# booster_2_01.net
KiCad netlist of a schematic drawn in EAGLE
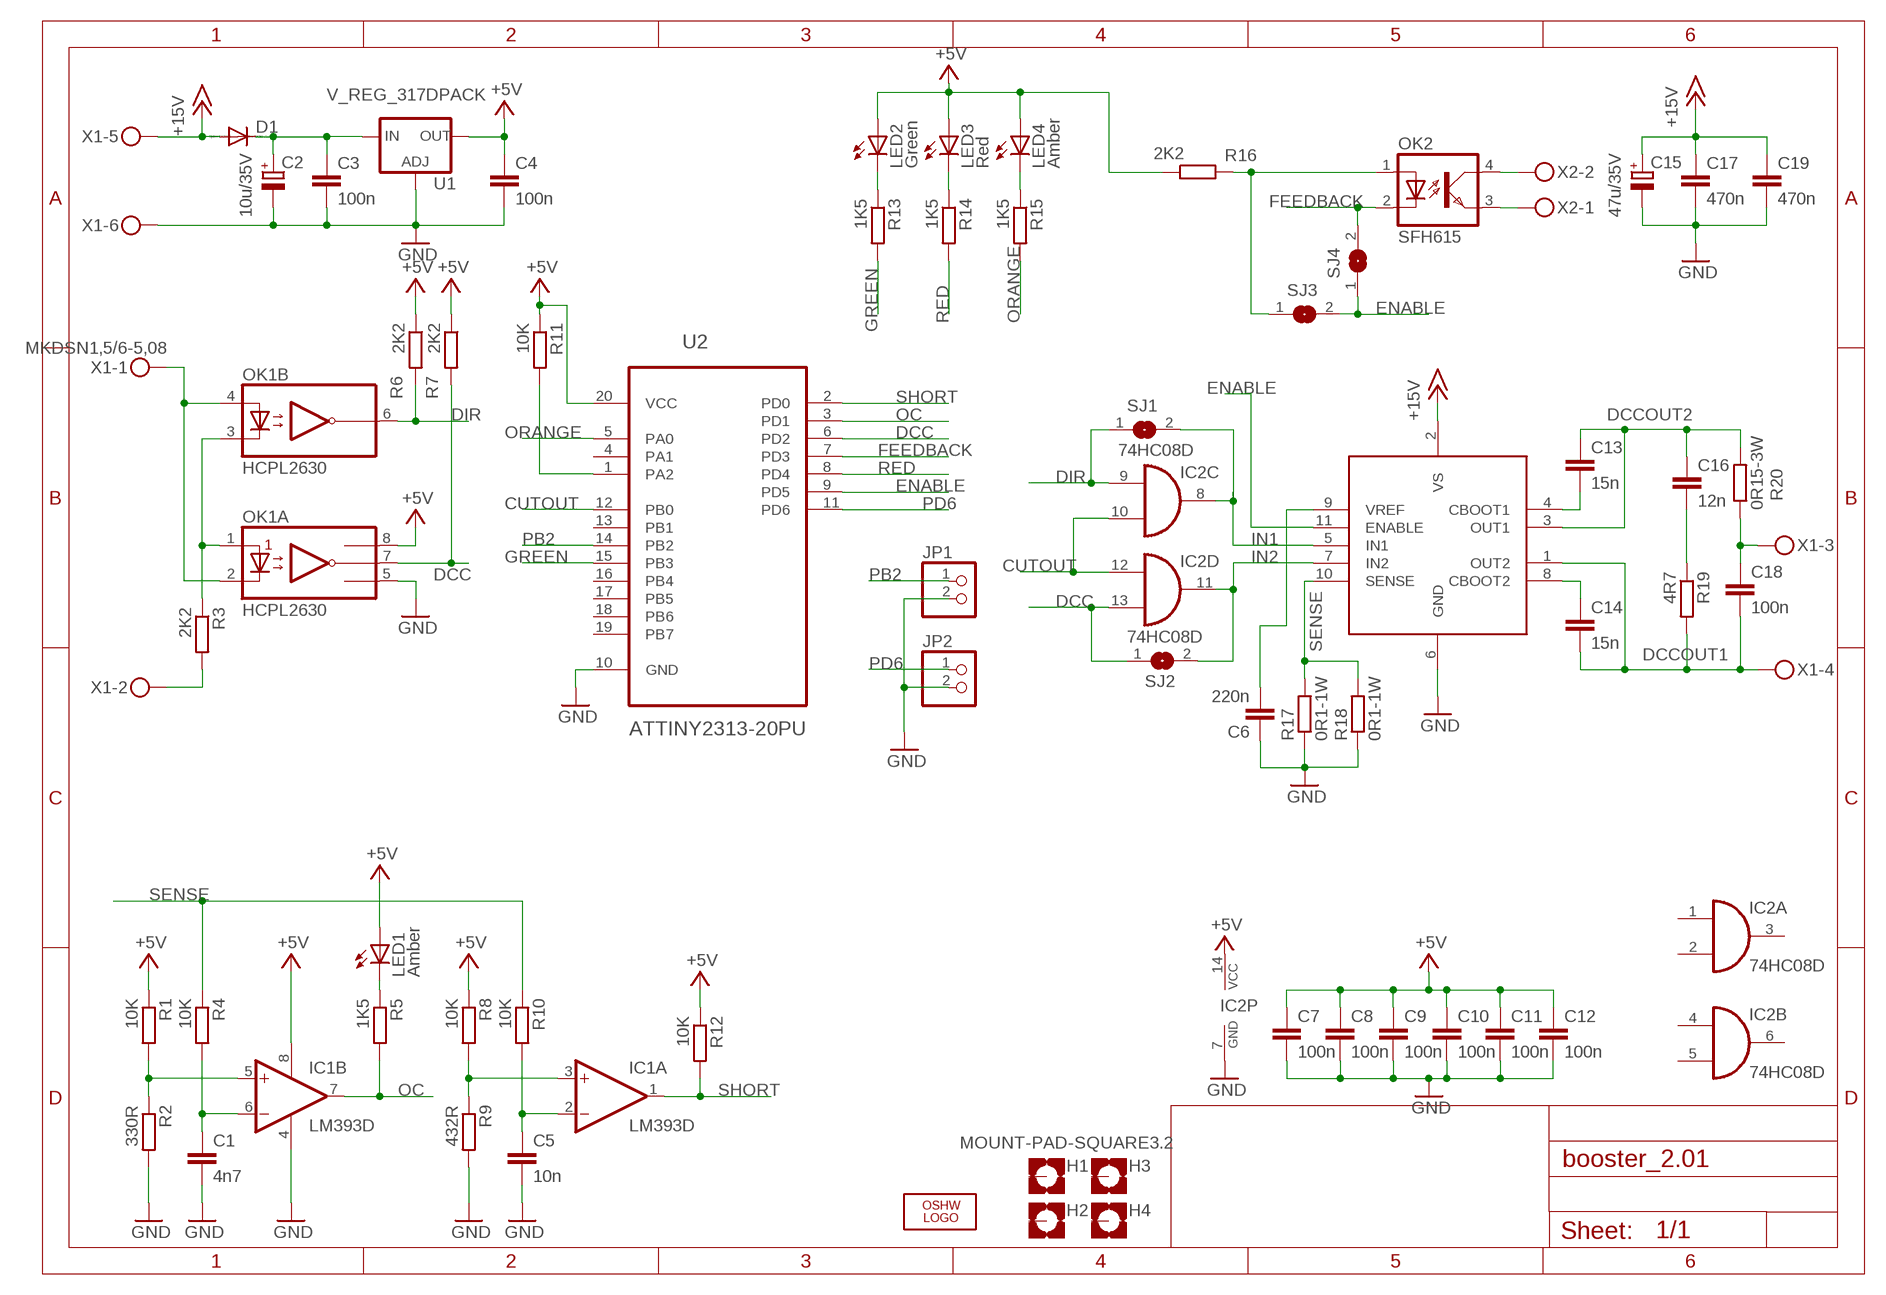
[diagram p0: schematic, sheet 1]

(export (version "E")
  (design (tool "Eeschema 10.0.6"))
  (components
    (comp (ref "C1")
      (value "4n7")
      (footprint "eagle-import:C0805")
      (libsource (lib "eagle-import") (part "C-EUC0805"))
    )
    (comp (ref "C2")
      (value "10u/35V")
      (footprint "eagle-import:E2,5-5")
      (libsource (lib "eagle-import") (part "CPOL-EUE2.5-5"))
    )
    (comp (ref "C3")
      (value "100n")
      (footprint "eagle-import:C0805")
      (libsource (lib "eagle-import") (part "C-EUC0805"))
    )
    (comp (ref "C4")
      (value "100n")
      (footprint "eagle-import:C0805")
      (libsource (lib "eagle-import") (part "C-EUC0805"))
    )
    (comp (ref "C5")
      (value "10n")
      (footprint "eagle-import:C0805")
      (libsource (lib "eagle-import") (part "C-EUC0805"))
    )
    (comp (ref "C6")
      (value "220n")
      (footprint "eagle-import:C0805")
      (libsource (lib "eagle-import") (part "C-EUC0805"))
    )
    (comp (ref "C7")
      (value "100n")
      (footprint "eagle-import:C0805")
      (libsource (lib "eagle-import") (part "C-EUC0805"))
    )
    (comp (ref "C8")
      (value "100n")
      (footprint "eagle-import:C0805")
      (libsource (lib "eagle-import") (part "C-EUC0805"))
    )
    (comp (ref "C9")
      (value "100n")
      (footprint "eagle-import:C0805")
      (libsource (lib "eagle-import") (part "C-EUC0805"))
    )
    (comp (ref "C10")
      (value "100n")
      (footprint "eagle-import:C0805")
      (libsource (lib "eagle-import") (part "C-EUC0805"))
    )
    (comp (ref "C11")
      (value "100n")
      (footprint "eagle-import:C0805")
      (libsource (lib "eagle-import") (part "C-EUC0805"))
    )
    (comp (ref "C12")
      (value "100n")
      (footprint "eagle-import:C0805")
      (libsource (lib "eagle-import") (part "C-EUC0805"))
    )
    (comp (ref "C13")
      (value "15n")
      (footprint "eagle-import:C0805")
      (libsource (lib "eagle-import") (part "C-EUC0805"))
    )
    (comp (ref "C14")
      (value "15n")
      (footprint "eagle-import:C0805")
      (libsource (lib "eagle-import") (part "C-EUC0805"))
    )
    (comp (ref "C15")
      (value "47u/35V")
      (footprint "eagle-import:E2,5-5")
      (libsource (lib "eagle-import") (part "CPOL-EUE2.5-5"))
    )
    (comp (ref "C16")
      (value "12n")
      (footprint "eagle-import:C0805")
      (libsource (lib "eagle-import") (part "C-EUC0805"))
    )
    (comp (ref "C17")
      (value "470n")
      (footprint "eagle-import:C1812")
      (libsource (lib "eagle-import") (part "rcl_334_C-EUC1812"))
    )
    (comp (ref "C18")
      (value "100n")
      (footprint "eagle-import:C0805")
      (libsource (lib "eagle-import") (part "C-EUC0805"))
    )
    (comp (ref "C19")
      (value "470n")
      (footprint "eagle-import:C1812")
      (libsource (lib "eagle-import") (part "rcl_334_C-EUC1812"))
    )
    (comp (ref "D1")
      (value "DIODE-SMB")
      (footprint "eagle-import:SMB")
      (libsource (lib "eagle-import") (part "DIODE-SMB"))
    )
    (comp (ref "H1")
      (value "MOUNT-PAD-SQUARE3.2")
      (footprint "eagle-import:3,2-PAD-SQUARE")
      (libsource (lib "eagle-import") (part "MOUNT-PAD-SQUARE3.2"))
    )
    (comp (ref "H2")
      (value "MOUNT-PAD-SQUARE3.2")
      (footprint "eagle-import:3,2-PAD-SQUARE")
      (libsource (lib "eagle-import") (part "MOUNT-PAD-SQUARE3.2"))
    )
    (comp (ref "H3")
      (value "MOUNT-PAD-SQUARE3.2")
      (footprint "eagle-import:3,2-PAD-SQUARE")
      (libsource (lib "eagle-import") (part "MOUNT-PAD-SQUARE3.2"))
    )
    (comp (ref "H4")
      (value "MOUNT-PAD-SQUARE3.2")
      (footprint "eagle-import:3,2-PAD-SQUARE")
      (libsource (lib "eagle-import") (part "MOUNT-PAD-SQUARE3.2"))
    )
    (comp (ref "IC1")
      (value "LM393D")
      (footprint "eagle-import:SO08")
      (libsource (lib "eagle-import") (part "LM393D"))
    )
    (comp (ref "IC2")
      (value "74HC08D")
      (footprint "eagle-import:SO14")
      (libsource (lib "eagle-import") (part "7408DHC"))
    )
    (comp (ref "JP1")
      (value "PINHD-1X2")
      (footprint "eagle-import:1X02")
      (libsource (lib "eagle-import") (part "PINHD-1X2"))
    )
    (comp (ref "JP2")
      (value "PINHD-1X2")
      (footprint "eagle-import:1X02")
      (libsource (lib "eagle-import") (part "PINHD-1X2"))
    )
    (comp (ref "LED1")
      (value "Amber")
      (footprint "eagle-import:LED3MM")
      (libsource (lib "eagle-import") (part "LED3MM"))
    )
    (comp (ref "LED2")
      (value "Green")
      (footprint "eagle-import:LED3MM")
      (libsource (lib "eagle-import") (part "LED3MM"))
    )
    (comp (ref "LED3")
      (value "Red")
      (footprint "eagle-import:LED3MM")
      (libsource (lib "eagle-import") (part "LED3MM"))
    )
    (comp (ref "LED4")
      (value "Amber")
      (footprint "eagle-import:LED3MM")
      (libsource (lib "eagle-import") (part "LED3MM"))
    )
    (comp (ref "LOGO1")
      (value "OSHW_LOGO_6MILX0200-NT")
      (footprint "eagle-import:OSHW_6X200_NOTEXT")
      (libsource (lib "eagle-import") (part "OSHW_LOGO_6MILX0200-NT"))
    )
    (comp (ref "OK1")
      (value "HCPL2630")
      (footprint "eagle-import:DIL08")
      (fields (field (name "MF") "AGILENT TECHNOLOGIES") (field (name "MPN") "HCPL-2630-000E"))
      (libsource (lib "eagle-import") (part "HCPL2630"))
    )
    (comp (ref "OK2")
      (value "SFH615")
      (footprint "eagle-import:DIL04")
      (fields (field (name "MPN") "SFH615A-2"))
      (libsource (lib "eagle-import") (part "SFH615"))
    )
    (comp (ref "R1")
      (value "10K")
      (footprint "eagle-import:R0805")
      (libsource (lib "eagle-import") (part "R-EU_R0805"))
    )
    (comp (ref "R2")
      (value "330R")
      (footprint "eagle-import:R0805")
      (libsource (lib "eagle-import") (part "R-EU_R0805"))
    )
    (comp (ref "R3")
      (value "2K2")
      (footprint "eagle-import:R0805")
      (libsource (lib "eagle-import") (part "R-EU_R0805"))
    )
    (comp (ref "R4")
      (value "10K")
      (footprint "eagle-import:R0805")
      (libsource (lib "eagle-import") (part "R-EU_R0805"))
    )
    (comp (ref "R5")
      (value "1K5")
      (footprint "eagle-import:R0805")
      (libsource (lib "eagle-import") (part "R-EU_R0805"))
    )
    (comp (ref "R6")
      (value "2K2")
      (footprint "eagle-import:R0805")
      (libsource (lib "eagle-import") (part "R-EU_R0805"))
    )
    (comp (ref "R7")
      (value "2K2")
      (footprint "eagle-import:R0805")
      (libsource (lib "eagle-import") (part "R-EU_R0805"))
    )
    (comp (ref "R8")
      (value "10K")
      (footprint "eagle-import:R0805")
      (libsource (lib "eagle-import") (part "R-EU_R0805"))
    )
    (comp (ref "R9")
      (value "432R")
      (footprint "eagle-import:R0805")
      (libsource (lib "eagle-import") (part "R-EU_R0805"))
    )
    (comp (ref "R10")
      (value "10K")
      (footprint "eagle-import:R0805")
      (libsource (lib "eagle-import") (part "R-EU_R0805"))
    )
    (comp (ref "R11")
      (value "10K")
      (footprint "eagle-import:R0805")
      (libsource (lib "eagle-import") (part "R-EU_R0805"))
    )
    (comp (ref "R12")
      (value "10K")
      (footprint "eagle-import:R0805")
      (libsource (lib "eagle-import") (part "R-EU_R0805"))
    )
    (comp (ref "R13")
      (value "1K5")
      (footprint "eagle-import:R0805")
      (libsource (lib "eagle-import") (part "R-EU_R0805"))
    )
    (comp (ref "R14")
      (value "1K5")
      (footprint "eagle-import:R0805")
      (libsource (lib "eagle-import") (part "R-EU_R0805"))
    )
    (comp (ref "R15")
      (value "1K5")
      (footprint "eagle-import:R0805")
      (libsource (lib "eagle-import") (part "R-EU_R0805"))
    )
    (comp (ref "R16")
      (value "2K2")
      (footprint "eagle-import:R0805")
      (libsource (lib "eagle-import") (part "R-EU_R0805"))
    )
    (comp (ref "R17")
      (value "0R1-1W")
      (footprint "eagle-import:R2512")
      (libsource (lib "eagle-import") (part "rcl_334_R-EU_R2512"))
    )
    (comp (ref "R18")
      (value "0R1-1W")
      (footprint "eagle-import:R2512")
      (libsource (lib "eagle-import") (part "rcl_334_R-EU_R2512"))
    )
    (comp (ref "R19")
      (value "4R7")
      (footprint "eagle-import:R0805")
      (libsource (lib "eagle-import") (part "R-EU_R0805"))
    )
    (comp (ref "R20")
      (value "0R15-3W")
      (footprint "eagle-import:P0817V")
      (libsource (lib "eagle-import") (part "rcl_334_R-EU_0817/7V"))
    )
    (comp (ref "SJ1") (value "SJ") (footprint "eagle-import:SJ") (libsource (lib "eagle-import") (part "SJ")))
    (comp (ref "SJ2") (value "SJ") (footprint "eagle-import:SJ") (libsource (lib "eagle-import") (part "SJ")))
    (comp (ref "SJ3") (value "SJ") (footprint "eagle-import:SJ") (libsource (lib "eagle-import") (part "SJ")))
    (comp (ref "SJ4") (value "SJ") (footprint "eagle-import:SJ") (libsource (lib "eagle-import") (part "SJ")))
    (comp (ref "U1")
      (value "V_REG_317DPACK")
      (footprint "eagle-import:V-REG_DPACK")
      (libsource (lib "eagle-import") (part "V_REG_317DPACK"))
    )
    (comp (ref "U2")
      (value "ATTINY2313-20PU")
      (footprint "eagle-import:DIP254P762X533-20")
      (libsource (lib "eagle-import") (part "ATTINY2313-20PU"))
    )
    (comp (ref "U3")
      (value "L6203")
      (footprint "eagle-import:ZIP_11")
      (fields (field (name "MANUFACTURER") "STM"))
      (libsource (lib "eagle-import") (part "L6203"))
    )
    (comp (ref "X1")
      (value "MKDSN1,5/6-5,08")
      (footprint "eagle-import:MKDSN1,5_6-5,08")
      (libsource (lib "eagle-import") (part "MKDSN1,5/6-5,08"))
    )
    (comp (ref "X2")
      (value "MKDSN1,5/2-5,08")
      (footprint "eagle-import:MKDSN1,5_2-5,08")
      (libsource (lib "eagle-import") (part "MKDSN1,5/2-5,08"))
    )
  )
  (nets
    (net (code "1") (name "+5V") (class "Default")
      (node (ref "C10") (pin "1") (pinfunction "1_1") (pintype "passive"))
      (node (ref "C11") (pin "1") (pinfunction "1_1") (pintype "passive"))
      (node (ref "C12") (pin "1") (pinfunction "1_1") (pintype "passive"))
      (node (ref "C4") (pin "1") (pinfunction "1_1") (pintype "passive"))
      (node (ref "C7") (pin "1") (pinfunction "1_1") (pintype "passive"))
      (node (ref "C8") (pin "1") (pinfunction "1_1") (pintype "passive"))
      (node (ref "C9") (pin "1") (pinfunction "1_1") (pintype "passive"))
      (node (ref "IC1") (pin "8") (pinfunction "V+_8") (pintype "power_in"))
      (node (ref "IC2") (pin "14") (pinfunction "VCC_14") (pintype "power_in"))
      (node (ref "LED1") (pin "A") (pinfunction "A_A") (pintype "passive"))
      (node (ref "LED2") (pin "A") (pinfunction "A_A") (pintype "passive"))
      (node (ref "LED3") (pin "A") (pinfunction "A_A") (pintype "passive"))
      (node (ref "LED4") (pin "A") (pinfunction "A_A") (pintype "passive"))
      (node (ref "OK1") (pin "8") (pinfunction "VCC_8") (pintype "passive"))
      (node (ref "R1") (pin "1") (pinfunction "1_1") (pintype "passive"))
      (node (ref "R11") (pin "1") (pinfunction "1_1") (pintype "passive"))
      (node (ref "R12") (pin "1") (pinfunction "1_1") (pintype "passive"))
      (node (ref "R16") (pin "1") (pinfunction "1_1") (pintype "passive"))
      (node (ref "R6") (pin "1") (pinfunction "1_1") (pintype "passive"))
      (node (ref "R7") (pin "1") (pinfunction "1_1") (pintype "passive"))
      (node (ref "R8") (pin "1") (pinfunction "1_1") (pintype "passive"))
      (node (ref "U1") (pin "4") (pinfunction "OUT_4") (pintype "output"))
      (node (ref "U2") (pin "20") (pinfunction "VCC_20") (pintype "power_in"))
    )
    (net (code "2") (name "+15V") (class "Default")
      (node (ref "C15") (pin "+") (pinfunction "+_+") (pintype "passive"))
      (node (ref "C17") (pin "1") (pinfunction "1_1") (pintype "passive"))
      (node (ref "C19") (pin "1") (pinfunction "1_1") (pintype "passive"))
      (node (ref "D1") (pin "A") (pinfunction "A_A") (pintype "passive"))
      (node (ref "U3") (pin "2") (pinfunction "VS_2") (pintype "power_in"))
      (node (ref "X1") (pin "5") (pinfunction "KL_5") (pintype "passive"))
    )
    (net (code "3") (name "/CUTOUT") (class "Default")
      (node (ref "IC2") (pin "10") (pinfunction "I1_10") (pintype "input"))
      (node (ref "IC2") (pin "12") (pinfunction "I0_12") (pintype "input"))
      (node (ref "U2") (pin "12") (pinfunction "PB0_12") (pintype "bidirectional"))
    )
    (net (code "4") (name "/DCC") (class "Default")
      (node (ref "IC2") (pin "13") (pinfunction "I1_13") (pintype "input"))
      (node (ref "OK1") (pin "7") (pinfunction "VO1_7") (pintype "passive"))
      (node (ref "R7") (pin "2") (pinfunction "2_2") (pintype "passive"))
      (node (ref "SJ2") (pin "1") (pinfunction "1_1") (pintype "passive"))
      (node (ref "U2") (pin "6") (pinfunction "PD2_6") (pintype "bidirectional"))
    )
    (net (code "5") (name "/DCCOUT1") (class "Default")
      (node (ref "C14") (pin "2") (pinfunction "2_2") (pintype "passive"))
      (node (ref "C18") (pin "2") (pinfunction "2_2") (pintype "passive"))
      (node (ref "R19") (pin "2") (pinfunction "2_2") (pintype "passive"))
      (node (ref "U3") (pin "1") (pinfunction "OUT2_1") (pintype "output"))
      (node (ref "X1") (pin "4") (pinfunction "KL_4") (pintype "passive"))
    )
    (net (code "6") (name "/DCCOUT2") (class "Default")
      (node (ref "C13") (pin "1") (pinfunction "1_1") (pintype "passive"))
      (node (ref "C16") (pin "1") (pinfunction "1_1") (pintype "passive"))
      (node (ref "R20") (pin "2") (pinfunction "2_2") (pintype "passive"))
      (node (ref "U3") (pin "3") (pinfunction "OUT1_3") (pintype "output"))
    )
    (net (code "7") (name "/DIR") (class "Default")
      (node (ref "IC2") (pin "9") (pinfunction "I0_9") (pintype "input"))
      (node (ref "OK1") (pin "6") (pinfunction "VO2_6") (pintype "passive"))
      (node (ref "R6") (pin "2") (pinfunction "2_2") (pintype "passive"))
      (node (ref "SJ1") (pin "1") (pinfunction "1_1") (pintype "passive"))
    )
    (net (code "8") (name "/ENABLE") (class "Default")
      (node (ref "SJ3") (pin "2") (pinfunction "2_2") (pintype "passive"))
      (node (ref "SJ4") (pin "1") (pinfunction "1_1") (pintype "passive"))
      (node (ref "U2") (pin "9") (pinfunction "PD5_9") (pintype "bidirectional"))
      (node (ref "U3") (pin "11") (pinfunction "ENABLE_11") (pintype "input"))
    )
    (net (code "9") (name "/FEEDBACK") (class "Default")
      (node (ref "OK2") (pin "2") (pinfunction "C_2") (pintype "passive"))
      (node (ref "SJ4") (pin "2") (pinfunction "2_2") (pintype "passive"))
      (node (ref "U2") (pin "7") (pinfunction "PD3_7") (pintype "bidirectional"))
    )
    (net (code "10") (name "/GREEN") (class "Default")
      (node (ref "R13") (pin "2") (pinfunction "2_2") (pintype "passive"))
      (node (ref "U2") (pin "15") (pinfunction "PB3_15") (pintype "bidirectional"))
    )
    (net (code "11") (name "/IN1") (class "Default")
      (node (ref "IC2") (pin "8") (pinfunction "O_8") (pintype "output"))
      (node (ref "SJ1") (pin "2") (pinfunction "2_2") (pintype "passive"))
      (node (ref "U3") (pin "5") (pinfunction "IN1_5") (pintype "input"))
    )
    (net (code "12") (name "/IN2") (class "Default")
      (node (ref "IC2") (pin "11") (pinfunction "O_11") (pintype "output"))
      (node (ref "SJ2") (pin "2") (pinfunction "2_2") (pintype "passive"))
      (node (ref "U3") (pin "7") (pinfunction "IN2_7") (pintype "input"))
    )
    (net (code "13") (name "/OC") (class "Default")
      (node (ref "IC1") (pin "7") (pinfunction "OUT_7") (pintype "output"))
      (node (ref "R5") (pin "2") (pinfunction "2_2") (pintype "passive"))
      (node (ref "U2") (pin "3") (pinfunction "PD1_3") (pintype "bidirectional"))
    )
    (net (code "14") (name "/ORANGE") (class "Default")
      (node (ref "R15") (pin "2") (pinfunction "2_2") (pintype "passive"))
      (node (ref "U2") (pin "5") (pinfunction "PA0_5") (pintype "bidirectional"))
    )
    (net (code "15") (name "/PB2") (class "Default")
      (node (ref "JP1") (pin "1") (pinfunction "1_1") (pintype "passive"))
      (node (ref "U2") (pin "14") (pinfunction "PB2_14") (pintype "bidirectional"))
    )
    (net (code "16") (name "/PD6") (class "Default")
      (node (ref "JP2") (pin "1") (pinfunction "1_1") (pintype "passive"))
      (node (ref "U2") (pin "11") (pinfunction "PD6_11") (pintype "bidirectional"))
    )
    (net (code "17") (name "/RED") (class "Default")
      (node (ref "R14") (pin "2") (pinfunction "2_2") (pintype "passive"))
      (node (ref "U2") (pin "8") (pinfunction "PD4_8") (pintype "bidirectional"))
    )
    (net (code "18") (name "/SENSE") (class "Default")
      (node (ref "R10") (pin "1") (pinfunction "1_1") (pintype "passive"))
      (node (ref "R17") (pin "2") (pinfunction "2_2") (pintype "passive"))
      (node (ref "R18") (pin "2") (pinfunction "2_2") (pintype "passive"))
      (node (ref "R4") (pin "1") (pinfunction "1_1") (pintype "passive"))
      (node (ref "U3") (pin "10") (pinfunction "SENSE_10") (pintype "input"))
    )
    (net (code "19") (name "/SHORT") (class "Default")
      (node (ref "IC1") (pin "1") (pinfunction "OUT_1") (pintype "output"))
      (node (ref "R12") (pin "2") (pinfunction "2_2") (pintype "passive"))
      (node (ref "U2") (pin "2") (pinfunction "PD0_2") (pintype "bidirectional"))
    )
    (net (code "20") (name "GND") (class "Default")
      (node (ref "C1") (pin "2") (pinfunction "2_2") (pintype "passive"))
      (node (ref "C10") (pin "2") (pinfunction "2_2") (pintype "passive"))
      (node (ref "C11") (pin "2") (pinfunction "2_2") (pintype "passive"))
      (node (ref "C12") (pin "2") (pinfunction "2_2") (pintype "passive"))
      (node (ref "C15") (pin "-") (pinfunction "-_-") (pintype "passive"))
      (node (ref "C17") (pin "2") (pinfunction "2_2") (pintype "passive"))
      (node (ref "C19") (pin "2") (pinfunction "2_2") (pintype "passive"))
      (node (ref "C2") (pin "-") (pinfunction "-_-") (pintype "passive"))
      (node (ref "C3") (pin "2") (pinfunction "2_2") (pintype "passive"))
      (node (ref "C4") (pin "2") (pinfunction "2_2") (pintype "passive"))
      (node (ref "C5") (pin "2") (pinfunction "2_2") (pintype "passive"))
      (node (ref "C6") (pin "1") (pinfunction "1_1") (pintype "passive"))
      (node (ref "C7") (pin "2") (pinfunction "2_2") (pintype "passive"))
      (node (ref "C8") (pin "2") (pinfunction "2_2") (pintype "passive"))
      (node (ref "C9") (pin "2") (pinfunction "2_2") (pintype "passive"))
      (node (ref "IC1") (pin "4") (pinfunction "V-_4") (pintype "power_in"))
      (node (ref "IC2") (pin "7") (pinfunction "GND_7") (pintype "power_in"))
      (node (ref "JP1") (pin "2") (pinfunction "2_2") (pintype "passive"))
      (node (ref "JP2") (pin "2") (pinfunction "2_2") (pintype "passive"))
      (node (ref "OK1") (pin "5") (pinfunction "GND_5") (pintype "passive"))
      (node (ref "R17") (pin "1") (pinfunction "1_1") (pintype "passive"))
      (node (ref "R18") (pin "1") (pinfunction "1_1") (pintype "passive"))
      (node (ref "R2") (pin "2") (pinfunction "2_2") (pintype "passive"))
      (node (ref "R9") (pin "2") (pinfunction "2_2") (pintype "passive"))
      (node (ref "U1") (pin "1") (pinfunction "ADJ_1") (pintype "input"))
      (node (ref "U2") (pin "10") (pinfunction "GND_10") (pintype "passive"))
      (node (ref "U3") (pin "6") (pinfunction "GND_6") (pintype "passive"))
      (node (ref "X1") (pin "6") (pinfunction "KL_6") (pintype "passive"))
    )
    (net (code "21") (name "Net-(C16-Pad2)") (class "Default")
      (node (ref "C16") (pin "2") (pinfunction "2_2") (pintype "passive"))
      (node (ref "R19") (pin "1") (pinfunction "1_1") (pintype "passive"))
    )
    (net (code "22") (name "Net-(IC1A-+IN)") (class "Default")
      (node (ref "IC1") (pin "3") (pinfunction "+IN_3") (pintype "input"))
      (node (ref "R8") (pin "2") (pinfunction "2_2") (pintype "passive"))
      (node (ref "R9") (pin "1") (pinfunction "1_1") (pintype "passive"))
    )
    (net (code "23") (name "Net-(IC1A--IN)") (class "Default")
      (node (ref "C5") (pin "1") (pinfunction "1_1") (pintype "passive"))
      (node (ref "IC1") (pin "2") (pinfunction "-IN_2") (pintype "input"))
      (node (ref "R10") (pin "2") (pinfunction "2_2") (pintype "passive"))
    )
    (net (code "24") (name "Net-(IC1B-+IN)") (class "Default")
      (node (ref "IC1") (pin "5") (pinfunction "+IN_5") (pintype "input"))
      (node (ref "R1") (pin "2") (pinfunction "2_2") (pintype "passive"))
      (node (ref "R2") (pin "1") (pinfunction "1_1") (pintype "passive"))
    )
    (net (code "25") (name "Net-(IC1B--IN)") (class "Default")
      (node (ref "C1") (pin "1") (pinfunction "1_1") (pintype "passive"))
      (node (ref "IC1") (pin "6") (pinfunction "-IN_6") (pintype "input"))
      (node (ref "R4") (pin "2") (pinfunction "2_2") (pintype "passive"))
    )
    (net (code "26") (name "Net-(LED1-C)") (class "Default")
      (node (ref "LED1") (pin "K") (pinfunction "C_K") (pintype "passive"))
      (node (ref "R5") (pin "1") (pinfunction "1_1") (pintype "passive"))
    )
    (net (code "27") (name "Net-(LED2-C)") (class "Default")
      (node (ref "LED2") (pin "K") (pinfunction "C_K") (pintype "passive"))
      (node (ref "R13") (pin "1") (pinfunction "1_1") (pintype "passive"))
    )
    (net (code "28") (name "Net-(LED3-C)") (class "Default")
      (node (ref "LED3") (pin "K") (pinfunction "C_K") (pintype "passive"))
      (node (ref "R14") (pin "1") (pinfunction "1_1") (pintype "passive"))
    )
    (net (code "29") (name "Net-(LED4-C)") (class "Default")
      (node (ref "LED4") (pin "K") (pinfunction "C_K") (pintype "passive"))
      (node (ref "R15") (pin "1") (pinfunction "1_1") (pintype "passive"))
    )
    (net (code "30") (name "Net-(OK1A-A1)") (class "Default")
      (node (ref "OK1") (pin "1") (pinfunction "A1_1") (pintype "passive"))
      (node (ref "OK1") (pin "3") (pinfunction "C2_3") (pintype "passive"))
      (node (ref "R3") (pin "1") (pinfunction "1_1") (pintype "passive"))
    )
    (net (code "31") (name "Net-(OK1A-C1)") (class "Default")
      (node (ref "OK1") (pin "2") (pinfunction "C1_2") (pintype "passive"))
      (node (ref "OK1") (pin "4") (pinfunction "A2_4") (pintype "passive"))
      (node (ref "X1") (pin "1") (pinfunction "KL_1") (pintype "passive"))
    )
    (net (code "32") (name "Net-(OK2-A)") (class "Default")
      (node (ref "OK2") (pin "1") (pinfunction "A_1") (pintype "passive"))
      (node (ref "R16") (pin "2") (pinfunction "2_2") (pintype "passive"))
      (node (ref "SJ3") (pin "1") (pinfunction "1_1") (pintype "passive"))
    )
    (net (code "33") (name "Net-(OK2-COL)") (class "Default")
      (node (ref "OK2") (pin "4") (pinfunction "COL_4") (pintype "passive"))
      (node (ref "X2") (pin "2") (pinfunction "KL_2") (pintype "passive"))
    )
    (net (code "34") (name "Net-(OK2-EMIT)") (class "Default")
      (node (ref "OK2") (pin "3") (pinfunction "EMIT_3") (pintype "passive"))
      (node (ref "X2") (pin "1") (pinfunction "KL_1") (pintype "passive"))
    )
    (net (code "35") (name "Net-(U1-IN)") (class "Default")
      (node (ref "C2") (pin "+") (pinfunction "+_+") (pintype "passive"))
      (node (ref "C3") (pin "1") (pinfunction "1_1") (pintype "passive"))
      (node (ref "D1") (pin "C") (pinfunction "C_C") (pintype "passive"))
      (node (ref "U1") (pin "3") (pinfunction "IN_3") (pintype "input"))
    )
    (net (code "36") (name "Net-(U2-PA2)") (class "Default")
      (node (ref "R11") (pin "2") (pinfunction "2_2") (pintype "passive"))
      (node (ref "U2") (pin "1") (pinfunction "PA2_1") (pintype "bidirectional"))
    )
    (net (code "37") (name "Net-(U3-CBOOT1)") (class "Default")
      (node (ref "C13") (pin "2") (pinfunction "2_2") (pintype "passive"))
      (node (ref "U3") (pin "4") (pinfunction "CBOOT1_4") (pintype "output"))
    )
    (net (code "38") (name "Net-(U3-CBOOT2)") (class "Default")
      (node (ref "C14") (pin "1") (pinfunction "1_1") (pintype "passive"))
      (node (ref "U3") (pin "8") (pinfunction "CBOOT2_8") (pintype "output"))
    )
    (net (code "39") (name "Net-(U3-VREF)") (class "Default")
      (node (ref "C6") (pin "2") (pinfunction "2_2") (pintype "passive"))
      (node (ref "U3") (pin "9") (pinfunction "VREF_9") (pintype "output"))
    )
    (net (code "40") (name "Net-(X1B-KL)") (class "Default")
      (node (ref "R3") (pin "2") (pinfunction "2_2") (pintype "passive"))
      (node (ref "X1") (pin "2") (pinfunction "KL_2") (pintype "passive"))
    )
    (net (code "41") (name "Net-(X1C-KL)") (class "Default")
      (node (ref "C18") (pin "1") (pinfunction "1_1") (pintype "passive"))
      (node (ref "R20") (pin "1") (pinfunction "1_1") (pintype "passive"))
      (node (ref "X1") (pin "3") (pinfunction "KL_3") (pintype "passive"))
    )
    (net (code "42") (name "unconnected-(H1-MOUNT-PadB3,2)") (class "Default")
      (node (ref "H1") (pin "B3,2") (pinfunction "MOUNT_B3,2") (pintype "passive"))
    )
    (net (code "43") (name "unconnected-(H2-MOUNT-PadB3,2)") (class "Default")
      (node (ref "H2") (pin "B3,2") (pinfunction "MOUNT_B3,2") (pintype "passive"))
    )
    (net (code "44") (name "unconnected-(H3-MOUNT-PadB3,2)") (class "Default")
      (node (ref "H3") (pin "B3,2") (pinfunction "MOUNT_B3,2") (pintype "passive"))
    )
    (net (code "45") (name "unconnected-(H4-MOUNT-PadB3,2)") (class "Default")
      (node (ref "H4") (pin "B3,2") (pinfunction "MOUNT_B3,2") (pintype "passive"))
    )
    (net (code "46") (name "unconnected-(IC2A-I0-Pad1)") (class "Default")
      (node (ref "IC2") (pin "1") (pinfunction "I0_1") (pintype "input"))
    )
    (net (code "47") (name "unconnected-(IC2A-I1-Pad2)") (class "Default")
      (node (ref "IC2") (pin "2") (pinfunction "I1_2") (pintype "input"))
    )
    (net (code "48") (name "unconnected-(IC2A-O-Pad3)") (class "Default")
      (node (ref "IC2") (pin "3") (pinfunction "O_3") (pintype "output"))
    )
    (net (code "49") (name "unconnected-(IC2B-I0-Pad4)") (class "Default")
      (node (ref "IC2") (pin "4") (pinfunction "I0_4") (pintype "input"))
    )
    (net (code "50") (name "unconnected-(IC2B-I1-Pad5)") (class "Default")
      (node (ref "IC2") (pin "5") (pinfunction "I1_5") (pintype "input"))
    )
    (net (code "51") (name "unconnected-(IC2B-O-Pad6)") (class "Default")
      (node (ref "IC2") (pin "6") (pinfunction "O_6") (pintype "output"))
    )
    (net (code "52") (name "unconnected-(U2-PA1-Pad4)") (class "Default")
      (node (ref "U2") (pin "4") (pinfunction "PA1_4") (pintype "bidirectional"))
    )
    (net (code "53") (name "unconnected-(U2-PB1-Pad13)") (class "Default")
      (node (ref "U2") (pin "13") (pinfunction "PB1_13") (pintype "bidirectional"))
    )
    (net (code "54") (name "unconnected-(U2-PB4-Pad16)") (class "Default")
      (node (ref "U2") (pin "16") (pinfunction "PB4_16") (pintype "bidirectional"))
    )
    (net (code "55") (name "unconnected-(U2-PB5-Pad17)") (class "Default")
      (node (ref "U2") (pin "17") (pinfunction "PB5_17") (pintype "bidirectional"))
    )
    (net (code "56") (name "unconnected-(U2-PB6-Pad18)") (class "Default")
      (node (ref "U2") (pin "18") (pinfunction "PB6_18") (pintype "bidirectional"))
    )
    (net (code "57") (name "unconnected-(U2-PB7-Pad19)") (class "Default")
      (node (ref "U2") (pin "19") (pinfunction "PB7_19") (pintype "bidirectional"))
    )
  )
)
